# Teensy3_based_M_M_board_v4_5.net
KiCad netlist of a schematic drawn in EAGLE
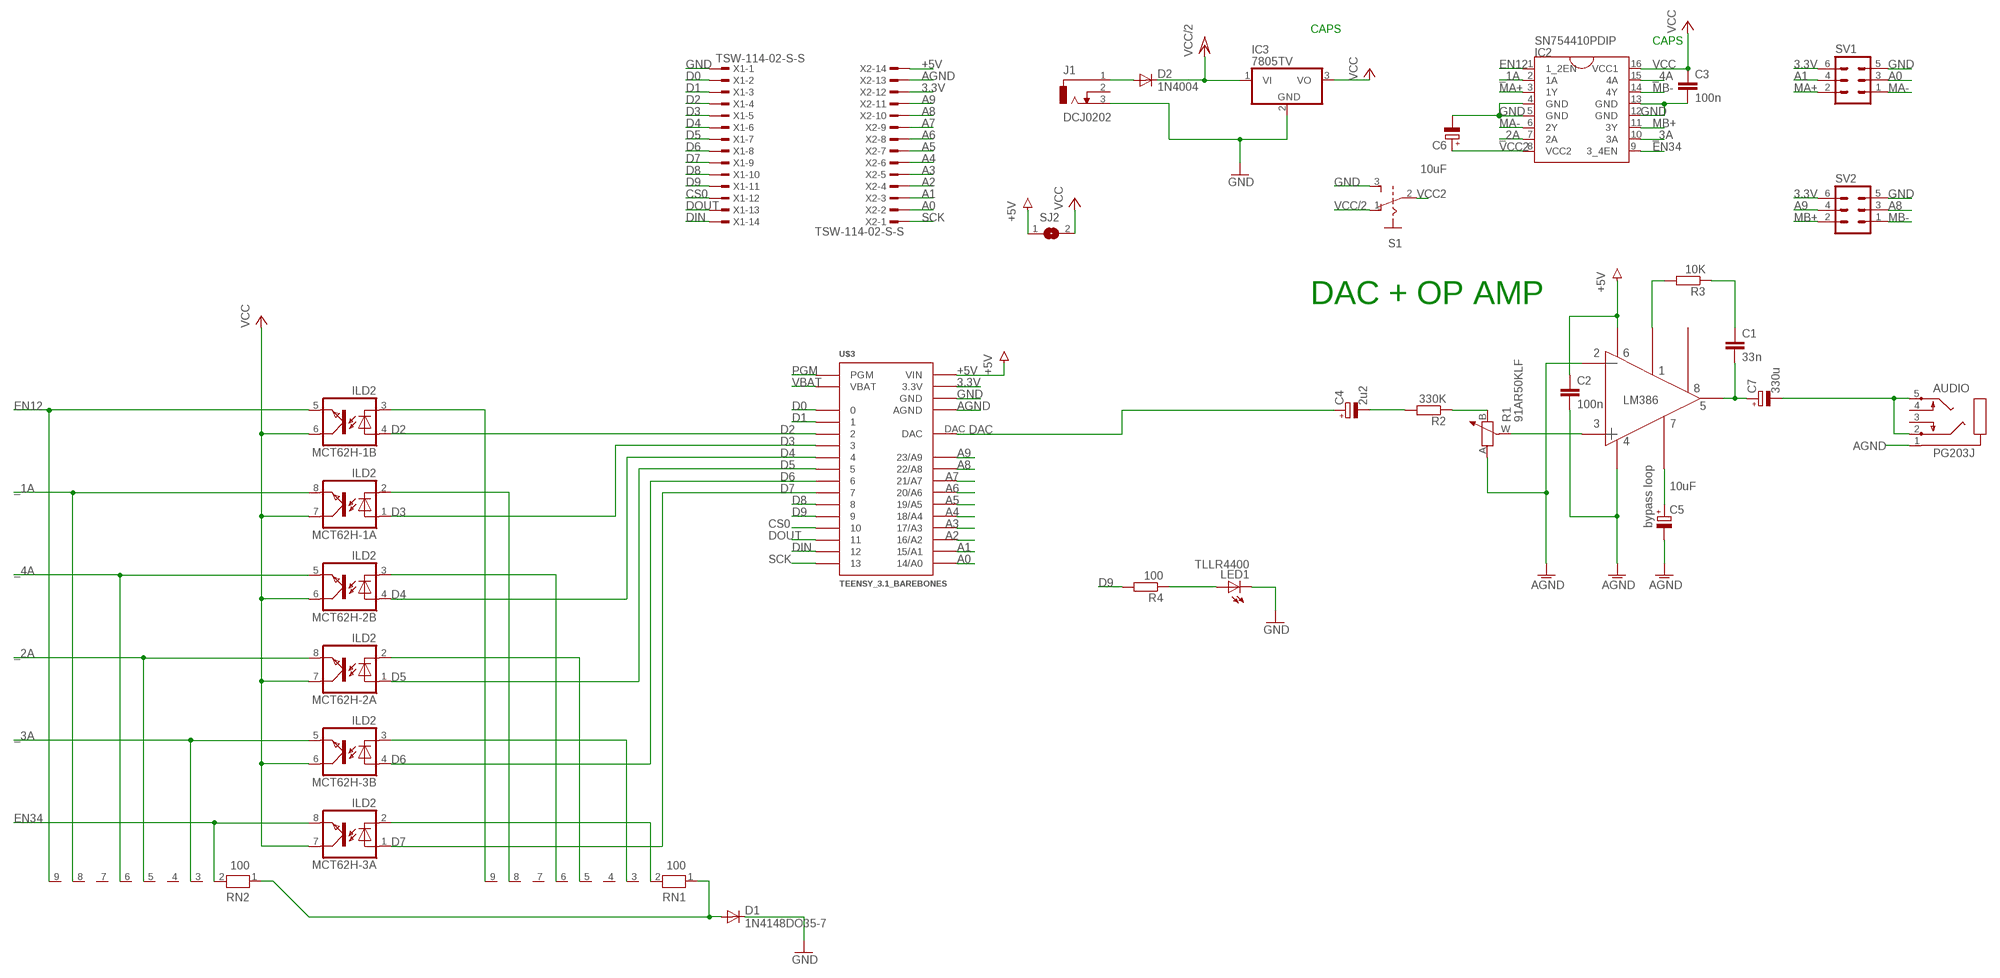
[diagram p0: schematic, sheet 1]

(export (version "E")
  (design (tool "Eeschema 10.0.6"))
  (components
    (comp (ref "AUDIO")
      (value "PG203J")
      (footprint "eagle-import:PG203J")
      (libsource (lib "eagle-import") (part "PG203J"))
    )
    (comp (ref "C1")
      (value "33n")
      (footprint "eagle-import:C050-030X075")
      (libsource (lib "eagle-import") (part "C-EU050-030X075"))
    )
    (comp (ref "C2")
      (value "100n")
      (footprint "eagle-import:C050-030X075")
      (libsource (lib "eagle-import") (part "C-EU050-030X075"))
    )
    (comp (ref "C3")
      (value "100n")
      (footprint "eagle-import:C050-030X075")
      (libsource (lib "eagle-import") (part "C-EU050-030X075"))
    )
    (comp (ref "C4")
      (value "2u2")
      (footprint "eagle-import:E2-5")
      (libsource (lib "eagle-import") (part "CPOL-EUE2-5"))
    )
    (comp (ref "C5")
      (value "10uF")
      (footprint "eagle-import:E2-5")
      (libsource (lib "eagle-import") (part "CPOL-EUE2-5"))
    )
    (comp (ref "C6")
      (value "10uF")
      (footprint "eagle-import:E2-5")
      (libsource (lib "eagle-import") (part "CPOL-EUE2-5"))
    )
    (comp (ref "C7")
      (value "330u")
      (footprint "eagle-import:E2,5-7")
      (libsource (lib "eagle-import") (part "CPOL-EUE2.5-7"))
    )
    (comp (ref "D1")
      (value "1N4148DO35-7")
      (footprint "eagle-import:DO35-7")
      (libsource (lib "eagle-import") (part "1N4148DO35-7"))
    )
    (comp (ref "D2")
      (value "1N4004")
      (footprint "eagle-import:DO41-10")
      (libsource (lib "eagle-import") (part "1N4004"))
    )
    (comp (ref "IC2")
      (value "SN754410PDIP")
      (footprint "eagle-import:DIL16")
      (libsource (lib "eagle-import") (part "SN754410PDIP"))
    )
    (comp (ref "IC3")
      (value "7805TV")
      (footprint "eagle-import:TO220V")
      (libsource (lib "eagle-import") (part "78TV05"))
    )
    (comp (ref "J1")
      (value "DCJ0202")
      (footprint "eagle-import:DCJ0202")
      (libsource (lib "eagle-import") (part "DCJ0202"))
    )
    (comp (ref "LED1")
      (value "TLLR4400")
      (footprint "eagle-import:LED3MM")
      (fields (field (name "MF") "VISHAY SEMICONDUCTOR"))
      (libsource (lib "eagle-import") (part "TLLR4400"))
    )
    (comp (ref "MCT62H-1")
      (value "ILD2")
      (footprint "eagle-import:DIL08")
      (libsource (lib "eagle-import") (part "ILD2"))
    )
    (comp (ref "MCT62H-2")
      (value "ILD2")
      (footprint "eagle-import:DIL08")
      (libsource (lib "eagle-import") (part "ILD2"))
    )
    (comp (ref "MCT62H-3")
      (value "ILD2")
      (footprint "eagle-import:DIL08")
      (libsource (lib "eagle-import") (part "ILD2"))
    )
    (comp (ref "R1")
      (value "91AR50KLF")
      (footprint "eagle-import:91AR50KLF")
      (libsource (lib "eagle-import") (part "91AR50KLF"))
    )
    (comp (ref "R2")
      (value "330K")
      (footprint "eagle-import:0207_7")
      (libsource (lib "eagle-import") (part "R-EU_0207/7"))
    )
    (comp (ref "R3")
      (value "10K")
      (footprint "eagle-import:0207_7")
      (libsource (lib "eagle-import") (part "R-EU_0207/7"))
    )
    (comp (ref "R4")
      (value "100")
      (footprint "eagle-import:0207_7")
      (libsource (lib "eagle-import") (part "R-EU_0207/7"))
    )
    (comp (ref "RN1")
      (value "100")
      (footprint "eagle-import:RN-9")
      (libsource (lib "eagle-import") (part "RN08"))
    )
    (comp (ref "RN2")
      (value "100")
      (footprint "eagle-import:RN-9")
      (libsource (lib "eagle-import") (part "RN08"))
    )
    (comp (ref "S1")
      (value "EG1218")
      (footprint "eagle-import:GF-126-0159")
      (libsource (lib "eagle-import") (part "EG1218"))
    )
    (comp (ref "SJ2") (value "SJ") (footprint "eagle-import:SJ") (libsource (lib "eagle-import") (part "SJ")))
    (comp (ref "SV1")
      (value "ML6")
      (footprint "eagle-import:ML6")
      (libsource (lib "eagle-import") (part "ML6"))
    )
    (comp (ref "SV2")
      (value "ML6")
      (footprint "eagle-import:ML6")
      (libsource (lib "eagle-import") (part "ML6"))
    )
    (comp (ref "U$2")
      (value "LM386")
      (footprint "eagle-import:LM386")
      (libsource (lib "eagle-import") (part "LM386OA"))
    )
    (comp (ref "U$3")
      (value "TEENSY_3.1_BAREBONES")
      (footprint "eagle-import:TEENSY_3.1_BAREBONES")
      (libsource (lib "eagle-import") (part "TEENSY_3.1_BAREBONES"))
    )
    (comp (ref "X1")
      (value "TSW-114-02-S-S")
      (footprint "eagle-import:TSW-114-02-S-S")
      (libsource (lib "eagle-import") (part "TSW-114-02-S-S"))
    )
    (comp (ref "X2")
      (value "TSW-114-02-S-S")
      (footprint "eagle-import:TSW-114-02-S-S")
      (libsource (lib "eagle-import") (part "TSW-114-02-S-S"))
    )
  )
  (nets
    (net (code "1") (name "+5V") (class "Default")
      (node (ref "C2") (pin "1") (pinfunction "1_1") (pintype "passive"))
      (node (ref "SJ2") (pin "1") (pinfunction "1_1") (pintype "passive"))
      (node (ref "U$2") (pin "6") (pinfunction "P$6_6") (pintype "bidirectional"))
      (node (ref "U$3") (pin "VIN") (pinfunction "VIN_VIN") (pintype "power_in"))
      (node (ref "X2") (pin "14") (pinfunction "1_14") (pintype "passive"))
    )
    (net (code "2") (name "/3.3V") (class "Default")
      (node (ref "SV1") (pin "6") (pinfunction "6_6") (pintype "passive"))
      (node (ref "SV2") (pin "6") (pinfunction "6_6") (pintype "passive"))
      (node (ref "U$3") (pin "3.3V1") (pinfunction "3.3V_3.3V1") (pintype "power_in"))
      (node (ref "U$3") (pin "3.3V2") (pinfunction "3.3V_3.3V2") (pintype "power_in"))
      (node (ref "X2") (pin "12") (pinfunction "1_12") (pintype "passive"))
    )
    (net (code "3") (name "/A0") (class "Default")
      (node (ref "SV1") (pin "3") (pinfunction "3_3") (pintype "passive"))
      (node (ref "U$3") (pin "14/A0") (pinfunction "14/A0_14/A0") (pintype "bidirectional"))
      (node (ref "X2") (pin "2") (pinfunction "1_2") (pintype "passive"))
    )
    (net (code "4") (name "/A1") (class "Default")
      (node (ref "SV1") (pin "4") (pinfunction "4_4") (pintype "passive"))
      (node (ref "U$3") (pin "15/A1") (pinfunction "15/A1_15/A1") (pintype "bidirectional"))
      (node (ref "X2") (pin "3") (pinfunction "1_3") (pintype "passive"))
    )
    (net (code "5") (name "/A2") (class "Default")
      (node (ref "U$3") (pin "16/A2") (pinfunction "16/A2_16/A2") (pintype "bidirectional"))
      (node (ref "X2") (pin "4") (pinfunction "1_4") (pintype "passive"))
    )
    (net (code "6") (name "/A3") (class "Default")
      (node (ref "U$3") (pin "17/A3") (pinfunction "17/A3_17/A3") (pintype "bidirectional"))
      (node (ref "X2") (pin "5") (pinfunction "1_5") (pintype "passive"))
    )
    (net (code "7") (name "/A4") (class "Default")
      (node (ref "U$3") (pin "18/A4") (pinfunction "18/A4_18/A4") (pintype "bidirectional"))
      (node (ref "X2") (pin "6") (pinfunction "1_6") (pintype "passive"))
    )
    (net (code "8") (name "/A5") (class "Default")
      (node (ref "U$3") (pin "19/A5") (pinfunction "19/A5_19/A5") (pintype "bidirectional"))
      (node (ref "X2") (pin "7") (pinfunction "1_7") (pintype "passive"))
    )
    (net (code "9") (name "/A6") (class "Default")
      (node (ref "U$3") (pin "20/A6") (pinfunction "20/A6_20/A6") (pintype "bidirectional"))
      (node (ref "X2") (pin "8") (pinfunction "1_8") (pintype "passive"))
    )
    (net (code "10") (name "/A7") (class "Default")
      (node (ref "U$3") (pin "21/A7") (pinfunction "21/A7_21/A7") (pintype "bidirectional"))
      (node (ref "X2") (pin "9") (pinfunction "1_9") (pintype "passive"))
    )
    (net (code "11") (name "/A8") (class "Default")
      (node (ref "SV2") (pin "3") (pinfunction "3_3") (pintype "passive"))
      (node (ref "U$3") (pin "22/A8") (pinfunction "22/A8_22/A8") (pintype "bidirectional"))
      (node (ref "X2") (pin "10") (pinfunction "1_10") (pintype "passive"))
    )
    (net (code "12") (name "/A9") (class "Default")
      (node (ref "SV2") (pin "4") (pinfunction "4_4") (pintype "passive"))
      (node (ref "U$3") (pin "23/A9") (pinfunction "23/A9_23/A9") (pintype "bidirectional"))
      (node (ref "X2") (pin "11") (pinfunction "1_11") (pintype "passive"))
    )
    (net (code "13") (name "/CS0") (class "Default")
      (node (ref "U$3") (pin "10") (pinfunction "10_10") (pintype "bidirectional"))
      (node (ref "X1") (pin "12") (pinfunction "1_12") (pintype "passive"))
    )
    (net (code "14") (name "/D0") (class "Default")
      (node (ref "U$3") (pin "0") (pinfunction "0_0") (pintype "bidirectional"))
      (node (ref "X1") (pin "2") (pinfunction "1_2") (pintype "passive"))
    )
    (net (code "15") (name "/D1") (class "Default")
      (node (ref "U$3") (pin "1") (pinfunction "1_1") (pintype "bidirectional"))
      (node (ref "X1") (pin "3") (pinfunction "1_3") (pintype "passive"))
    )
    (net (code "16") (name "/D2") (class "Default")
      (node (ref "MCT62H-1") (pin "4") (pinfunction "A_4") (pintype "passive"))
      (node (ref "U$3") (pin "2") (pinfunction "2_2") (pintype "bidirectional"))
      (node (ref "X1") (pin "4") (pinfunction "1_4") (pintype "passive"))
    )
    (net (code "17") (name "/D3") (class "Default")
      (node (ref "MCT62H-1") (pin "1") (pinfunction "A_1") (pintype "passive"))
      (node (ref "U$3") (pin "3") (pinfunction "3_3") (pintype "bidirectional"))
      (node (ref "X1") (pin "5") (pinfunction "1_5") (pintype "passive"))
    )
    (net (code "18") (name "/D4") (class "Default")
      (node (ref "MCT62H-2") (pin "4") (pinfunction "A_4") (pintype "passive"))
      (node (ref "U$3") (pin "4") (pinfunction "4_4") (pintype "bidirectional"))
      (node (ref "X1") (pin "6") (pinfunction "1_6") (pintype "passive"))
    )
    (net (code "19") (name "/D5") (class "Default")
      (node (ref "MCT62H-2") (pin "1") (pinfunction "A_1") (pintype "passive"))
      (node (ref "U$3") (pin "5") (pinfunction "5_5") (pintype "bidirectional"))
      (node (ref "X1") (pin "7") (pinfunction "1_7") (pintype "passive"))
    )
    (net (code "20") (name "/D6") (class "Default")
      (node (ref "MCT62H-3") (pin "4") (pinfunction "A_4") (pintype "passive"))
      (node (ref "U$3") (pin "6") (pinfunction "6_6") (pintype "bidirectional"))
      (node (ref "X1") (pin "8") (pinfunction "1_8") (pintype "passive"))
    )
    (net (code "21") (name "/D7") (class "Default")
      (node (ref "MCT62H-3") (pin "1") (pinfunction "A_1") (pintype "passive"))
      (node (ref "U$3") (pin "7") (pinfunction "7_7") (pintype "bidirectional"))
      (node (ref "X1") (pin "9") (pinfunction "1_9") (pintype "passive"))
    )
    (net (code "22") (name "/D8") (class "Default")
      (node (ref "U$3") (pin "8") (pinfunction "8_8") (pintype "bidirectional"))
      (node (ref "X1") (pin "10") (pinfunction "1_10") (pintype "passive"))
    )
    (net (code "23") (name "/D9") (class "Default")
      (node (ref "R4") (pin "2") (pinfunction "2_2") (pintype "passive"))
      (node (ref "U$3") (pin "9") (pinfunction "9_9") (pintype "bidirectional"))
      (node (ref "X1") (pin "11") (pinfunction "1_11") (pintype "passive"))
    )
    (net (code "24") (name "/DAC") (class "Default")
      (node (ref "C4") (pin "+") (pinfunction "+_+") (pintype "passive"))
      (node (ref "U$3") (pin "DAC") (pinfunction "DAC_DAC") (pintype "bidirectional"))
    )
    (net (code "25") (name "/DIN") (class "Default")
      (node (ref "U$3") (pin "12") (pinfunction "12_12") (pintype "bidirectional"))
      (node (ref "X1") (pin "14") (pinfunction "1_14") (pintype "passive"))
    )
    (net (code "26") (name "/DOUT") (class "Default")
      (node (ref "U$3") (pin "11") (pinfunction "11_11") (pintype "bidirectional"))
      (node (ref "X1") (pin "13") (pinfunction "1_13") (pintype "passive"))
    )
    (net (code "27") (name "/EN12") (class "Default")
      (node (ref "IC2") (pin "1") (pinfunction "1_2EN_1") (pintype "bidirectional"))
      (node (ref "MCT62H-1") (pin "5") (pinfunction "EMIT_5") (pintype "passive"))
      (node (ref "RN2") (pin "9") (pinfunction "9_9") (pintype "passive"))
    )
    (net (code "28") (name "/EN34") (class "Default")
      (node (ref "IC2") (pin "9") (pinfunction "3_4EN_9") (pintype "bidirectional"))
      (node (ref "MCT62H-3") (pin "8") (pinfunction "EMIT_8") (pintype "passive"))
      (node (ref "RN2") (pin "2") (pinfunction "2_2") (pintype "passive"))
    )
    (net (code "29") (name "/MA+") (class "Default")
      (node (ref "IC2") (pin "3") (pinfunction "1Y_3") (pintype "bidirectional"))
      (node (ref "SV1") (pin "2") (pinfunction "2_2") (pintype "passive"))
    )
    (net (code "30") (name "/MA-") (class "Default")
      (node (ref "IC2") (pin "6") (pinfunction "2Y_6") (pintype "bidirectional"))
      (node (ref "SV1") (pin "1") (pinfunction "1_1") (pintype "passive"))
    )
    (net (code "31") (name "/MB+") (class "Default")
      (node (ref "IC2") (pin "11") (pinfunction "3Y_11") (pintype "bidirectional"))
      (node (ref "SV2") (pin "2") (pinfunction "2_2") (pintype "passive"))
    )
    (net (code "32") (name "/MB-") (class "Default")
      (node (ref "IC2") (pin "14") (pinfunction "4Y_14") (pintype "bidirectional"))
      (node (ref "SV2") (pin "1") (pinfunction "1_1") (pintype "passive"))
    )
    (net (code "33") (name "/PGM") (class "Default")
      (node (ref "U$3") (pin "PGM") (pinfunction "PGM_PGM") (pintype "input"))
    )
    (net (code "34") (name "/SCK") (class "Default")
      (node (ref "U$3") (pin "13") (pinfunction "13_13") (pintype "bidirectional"))
      (node (ref "X2") (pin "1") (pinfunction "1_1") (pintype "passive"))
    )
    (net (code "35") (name "/VBAT") (class "Default")
      (node (ref "U$3") (pin "VBAT") (pinfunction "VBAT_VBAT") (pintype "power_in"))
    )
    (net (code "36") (name "/VCC2") (class "Default")
      (node (ref "C6") (pin "+") (pinfunction "+_+") (pintype "passive"))
      (node (ref "IC2") (pin "8") (pinfunction "VCC2_8") (pintype "bidirectional"))
      (node (ref "S1") (pin "2") (pinfunction "02_2") (pintype "passive"))
    )
    (net (code "37") (name "/_1A") (class "Default")
      (node (ref "IC2") (pin "2") (pinfunction "1A_2") (pintype "bidirectional"))
      (node (ref "MCT62H-1") (pin "8") (pinfunction "EMIT_8") (pintype "passive"))
      (node (ref "RN2") (pin "8") (pinfunction "8_8") (pintype "passive"))
    )
    (net (code "38") (name "/_2A") (class "Default")
      (node (ref "IC2") (pin "7") (pinfunction "2A_7") (pintype "bidirectional"))
      (node (ref "MCT62H-2") (pin "8") (pinfunction "EMIT_8") (pintype "passive"))
      (node (ref "RN2") (pin "5") (pinfunction "5_5") (pintype "passive"))
    )
    (net (code "39") (name "/_3A") (class "Default")
      (node (ref "IC2") (pin "10") (pinfunction "3A_10") (pintype "bidirectional"))
      (node (ref "MCT62H-3") (pin "5") (pinfunction "EMIT_5") (pintype "passive"))
      (node (ref "RN2") (pin "3") (pinfunction "3_3") (pintype "passive"))
    )
    (net (code "40") (name "/_4A") (class "Default")
      (node (ref "IC2") (pin "15") (pinfunction "4A_15") (pintype "bidirectional"))
      (node (ref "MCT62H-2") (pin "5") (pinfunction "EMIT_5") (pintype "passive"))
      (node (ref "RN2") (pin "6") (pinfunction "6_6") (pintype "passive"))
    )
    (net (code "41") (name "AGND") (class "Default")
      (node (ref "AUDIO") (pin "1") (pinfunction "1_1") (pintype "passive"))
      (node (ref "C2") (pin "2") (pinfunction "2_2") (pintype "passive"))
      (node (ref "C5") (pin "-") (pinfunction "-_-") (pintype "passive"))
      (node (ref "R1") (pin "A") (pinfunction "A_A") (pintype "passive"))
      (node (ref "U$2") (pin "2") (pinfunction "P$2_2") (pintype "bidirectional"))
      (node (ref "U$2") (pin "4") (pinfunction "P$4_4") (pintype "bidirectional"))
      (node (ref "U$3") (pin "AGND") (pinfunction "AGND_AGND") (pintype "power_in"))
      (node (ref "X2") (pin "13") (pinfunction "1_13") (pintype "passive"))
    )
    (net (code "42") (name "GND") (class "Default")
      (node (ref "C3") (pin "2") (pinfunction "2_2") (pintype "passive"))
      (node (ref "C6") (pin "-") (pinfunction "-_-") (pintype "passive"))
      (node (ref "D1") (pin "C") (pinfunction "C_C") (pintype "passive"))
      (node (ref "IC2") (pin "12") (pinfunction "GND_12") (pintype "bidirectional"))
      (node (ref "IC2") (pin "13") (pinfunction "GND_13") (pintype "bidirectional"))
      (node (ref "IC2") (pin "4") (pinfunction "GND_4") (pintype "bidirectional"))
      (node (ref "IC2") (pin "5") (pinfunction "GND_5") (pintype "bidirectional"))
      (node (ref "IC3") (pin "2") (pinfunction "GND_2") (pintype "passive"))
      (node (ref "J1") (pin "3") (pinfunction "3_3") (pintype "passive"))
      (node (ref "LED1") (pin "K") (pinfunction "C_K") (pintype "passive"))
      (node (ref "S1") (pin "3") (pinfunction "3_3") (pintype "passive"))
      (node (ref "SV1") (pin "5") (pinfunction "5_5") (pintype "passive"))
      (node (ref "SV2") (pin "5") (pinfunction "5_5") (pintype "passive"))
      (node (ref "U$3") (pin "GND1") (pinfunction "GND_GND1") (pintype "power_in"))
      (node (ref "U$3") (pin "GND2") (pinfunction "GND_GND2") (pintype "power_in"))
      (node (ref "X1") (pin "1") (pinfunction "1_1") (pintype "passive"))
    )
    (net (code "43") (name "Net-(AUDIO-Pad2)") (class "Default")
      (node (ref "AUDIO") (pin "2") (pinfunction "2_2") (pintype "passive"))
      (node (ref "AUDIO") (pin "5") (pinfunction "5_5") (pintype "passive"))
      (node (ref "C7") (pin "-") (pinfunction "-_-") (pintype "passive"))
    )
    (net (code "44") (name "Net-(C1-Pad1)") (class "Default")
      (node (ref "C1") (pin "1") (pinfunction "1_1") (pintype "passive"))
      (node (ref "R3") (pin "1") (pinfunction "1_1") (pintype "passive"))
    )
    (net (code "45") (name "Net-(C4-Pad-)") (class "Default")
      (node (ref "C4") (pin "-") (pinfunction "-_-") (pintype "passive"))
      (node (ref "R2") (pin "2") (pinfunction "2_2") (pintype "passive"))
    )
    (net (code "46") (name "Net-(D1-PadA)") (class "Default")
      (node (ref "D1") (pin "A") (pinfunction "A_A") (pintype "passive"))
      (node (ref "RN1") (pin "1") (pinfunction "1_1") (pintype "passive"))
      (node (ref "RN2") (pin "1") (pinfunction "1_1") (pintype "passive"))
    )
    (net (code "47") (name "Net-(D2-PadA)") (class "Default")
      (node (ref "D2") (pin "A") (pinfunction "A_A") (pintype "passive"))
      (node (ref "J1") (pin "1") (pinfunction "1_1") (pintype "passive"))
    )
    (net (code "48") (name "Net-(LED1-PadA)") (class "Default")
      (node (ref "LED1") (pin "A") (pinfunction "A_A") (pintype "passive"))
      (node (ref "R4") (pin "1") (pinfunction "1_1") (pintype "passive"))
    )
    (net (code "49") (name "Net-(MCT62H-1A-C)") (class "Default")
      (node (ref "MCT62H-1") (pin "2") (pinfunction "C_2") (pintype "passive"))
      (node (ref "RN1") (pin "8") (pinfunction "8_8") (pintype "passive"))
    )
    (net (code "50") (name "Net-(MCT62H-1B-C)") (class "Default")
      (node (ref "MCT62H-1") (pin "3") (pinfunction "C_3") (pintype "passive"))
      (node (ref "RN1") (pin "9") (pinfunction "9_9") (pintype "passive"))
    )
    (net (code "51") (name "Net-(MCT62H-2A-C)") (class "Default")
      (node (ref "MCT62H-2") (pin "2") (pinfunction "C_2") (pintype "passive"))
      (node (ref "RN1") (pin "5") (pinfunction "5_5") (pintype "passive"))
    )
    (net (code "52") (name "Net-(MCT62H-2B-C)") (class "Default")
      (node (ref "MCT62H-2") (pin "3") (pinfunction "C_3") (pintype "passive"))
      (node (ref "RN1") (pin "6") (pinfunction "6_6") (pintype "passive"))
    )
    (net (code "53") (name "Net-(MCT62H-3A-C)") (class "Default")
      (node (ref "MCT62H-3") (pin "2") (pinfunction "C_2") (pintype "passive"))
      (node (ref "RN1") (pin "2") (pinfunction "2_2") (pintype "passive"))
    )
    (net (code "54") (name "Net-(MCT62H-3B-C)") (class "Default")
      (node (ref "MCT62H-3") (pin "3") (pinfunction "C_3") (pintype "passive"))
      (node (ref "RN1") (pin "3") (pinfunction "3_3") (pintype "passive"))
    )
    (net (code "55") (name "Net-(R1-PadB)") (class "Default")
      (node (ref "R1") (pin "B") (pinfunction "B_B") (pintype "passive"))
      (node (ref "R2") (pin "1") (pinfunction "1_1") (pintype "passive"))
    )
    (net (code "56") (name "Net-(U$2-P$1)") (class "Default")
      (node (ref "R3") (pin "2") (pinfunction "2_2") (pintype "passive"))
      (node (ref "U$2") (pin "1") (pinfunction "P$1_1") (pintype "bidirectional"))
    )
    (net (code "57") (name "Net-(U$2-P$3)") (class "Default")
      (node (ref "R1") (pin "W") (pinfunction "W_W") (pintype "passive"))
      (node (ref "U$2") (pin "3") (pinfunction "P$3_3") (pintype "bidirectional"))
    )
    (net (code "58") (name "Net-(U$2-P$5)") (class "Default")
      (node (ref "C1") (pin "2") (pinfunction "2_2") (pintype "passive"))
      (node (ref "C7") (pin "+") (pinfunction "+_+") (pintype "passive"))
      (node (ref "U$2") (pin "5") (pinfunction "P$5_5") (pintype "bidirectional"))
    )
    (net (code "59") (name "Net-(U$2-P$7)") (class "Default")
      (node (ref "C5") (pin "+") (pinfunction "+_+") (pintype "passive"))
      (node (ref "U$2") (pin "7") (pinfunction "P$7_7") (pintype "bidirectional"))
    )
    (net (code "60") (name "VCC") (class "Default")
      (node (ref "C3") (pin "1") (pinfunction "1_1") (pintype "passive"))
      (node (ref "IC2") (pin "16") (pinfunction "VCC1_16") (pintype "bidirectional"))
      (node (ref "IC3") (pin "3") (pinfunction "VO_3") (pintype "passive"))
      (node (ref "MCT62H-1") (pin "6") (pinfunction "COL_6") (pintype "passive"))
      (node (ref "MCT62H-1") (pin "7") (pinfunction "COL_7") (pintype "passive"))
      (node (ref "MCT62H-2") (pin "6") (pinfunction "COL_6") (pintype "passive"))
      (node (ref "MCT62H-2") (pin "7") (pinfunction "COL_7") (pintype "passive"))
      (node (ref "MCT62H-3") (pin "6") (pinfunction "COL_6") (pintype "passive"))
      (node (ref "MCT62H-3") (pin "7") (pinfunction "COL_7") (pintype "passive"))
      (node (ref "SJ2") (pin "2") (pinfunction "2_2") (pintype "passive"))
    )
    (net (code "61") (name "VCC{slash}2") (class "Default")
      (node (ref "D2") (pin "C") (pinfunction "C_C") (pintype "passive"))
      (node (ref "IC3") (pin "1") (pinfunction "VI_1") (pintype "input"))
      (node (ref "S1") (pin "1") (pinfunction "1_1") (pintype "passive"))
    )
    (net (code "62") (name "unconnected-(AUDIO-Pad3)") (class "Default")
      (node (ref "AUDIO") (pin "3") (pinfunction "3_3") (pintype "passive"))
    )
    (net (code "63") (name "unconnected-(AUDIO-Pad4)") (class "Default")
      (node (ref "AUDIO") (pin "4") (pinfunction "4_4") (pintype "passive"))
    )
    (net (code "64") (name "unconnected-(J1-Pad2)") (class "Default")
      (node (ref "J1") (pin "2") (pinfunction "2_2") (pintype "passive"))
    )
    (net (code "65") (name "unconnected-(RN1-Pad4)") (class "Default")
      (node (ref "RN1") (pin "4") (pinfunction "4_4") (pintype "passive"))
    )
    (net (code "66") (name "unconnected-(RN1-Pad7)") (class "Default")
      (node (ref "RN1") (pin "7") (pinfunction "7_7") (pintype "passive"))
    )
    (net (code "67") (name "unconnected-(RN2-Pad4)") (class "Default")
      (node (ref "RN2") (pin "4") (pinfunction "4_4") (pintype "passive"))
    )
    (net (code "68") (name "unconnected-(RN2-Pad7)") (class "Default")
      (node (ref "RN2") (pin "7") (pinfunction "7_7") (pintype "passive"))
    )
    (net (code "69") (name "unconnected-(U$2-P$8-Pad8)") (class "Default")
      (node (ref "U$2") (pin "8") (pinfunction "P$8_8") (pintype "bidirectional"))
    )
  )
)
